# 171-5783.net
KiCad netlist of a schematic drawn in Altium Designer
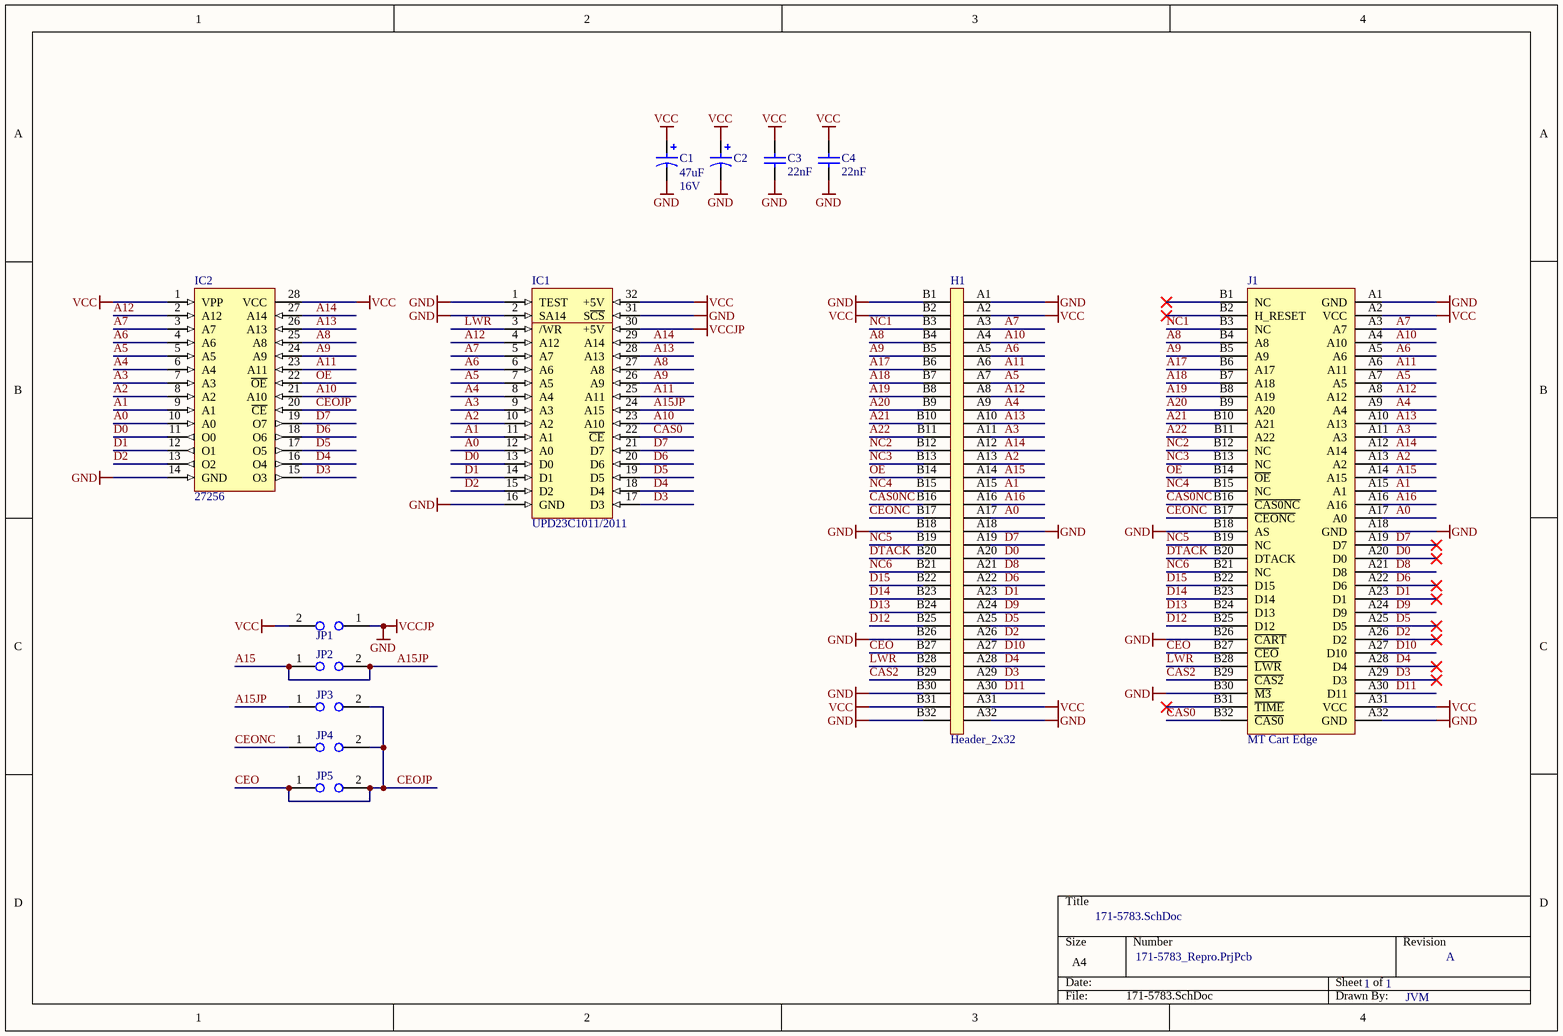
[diagram p0: 171-5783.SchDoc]

(export (version "E")
  (design (tool "Eeschema 10.0.6"))
  (components
    (comp (ref "C1")
      (value "47uF")
      (footprint "CapPol Mirror")
      (description "Polarized Capacitor, 2.54mm Pitch, 5mm Width, mirrored")
      (fields (field (name "VOLTAGE") "16V") (field (name "Comment") "Cap2.54P5.0D"))
      (libsource (lib "171-5782") (part "Cap2.54P5.0D_mirror"))
    )
    (comp (ref "C2")
      (value "Cap2.54P5.0D")
      (footprint "CapPol")
      (description "Polarized Capacitor, 2.54mm Pitch, 5mm Width")
      (libsource (lib "171-5782") (part "Cap2.54P5.0D"))
    )
    (comp (ref "C3")
      (value "22nF")
      (footprint "CapCer")
      (description "Capacitor (THT), Ceramic, 5.08mm Pitch")
      (fields (field (name "Comment") "CapCer"))
      (libsource (lib "171-5782") (part "CapCer"))
    )
    (comp (ref "C4")
      (value "22nF")
      (footprint "CapCer")
      (description "Capacitor (THT), Ceramic, 5.08mm Pitch")
      (fields (field (name "Comment") "CapCer"))
      (libsource (lib "171-5782") (part "CapCer"))
    )
    (comp (ref "H1")
      (value "Header_2x32")
      (footprint "Header_2x32")
      (libsource (lib "171-5782") (part "Header_2x32"))
    )
    (comp (ref "IC1")
      (value "UPD23C1011/2011")
      (footprint "UPD23C1011/2011")
      (description "SMS Mapper Mask Rom, Dual footprint")
      (libsource (lib "171-5782") (part "UPD23C1011/2011"))
    )
    (comp (ref "IC2")
      (value "27256")
      (footprint "27256")
      (description "256K EPROM")
      (libsource (lib "171-5782") (part "27256"))
    )
    (comp (ref "J1")
      (value "MT Cart Edge")
      (footprint "MT_Cart_Edge")
      (libsource (lib "171-5782") (part "MT_CART_EDGE_CON"))
    )
    (comp (ref "JP1")
      (value "SolderBridge")
      (footprint "SOLDER_BRIDGE")
      (description "Solder Bridge")
      (libsource (lib "171-5782") (part "SolderBridge"))
    )
    (comp (ref "JP2")
      (value "SolderBridge")
      (footprint "SOLDER_BRIDGE")
      (description "Solder Bridge")
      (libsource (lib "171-5782") (part "SolderBridge"))
    )
    (comp (ref "JP3")
      (value "SolderBridge")
      (footprint "SOLDER_BRIDGE")
      (description "Solder Bridge")
      (libsource (lib "171-5782") (part "SolderBridge"))
    )
    (comp (ref "JP4")
      (value "SolderBridge")
      (footprint "SOLDER_BRIDGE")
      (description "Solder Bridge")
      (libsource (lib "171-5782") (part "SolderBridge"))
    )
    (comp (ref "JP5")
      (value "SolderBridge")
      (footprint "SOLDER_BRIDGE")
      (description "Solder Bridge")
      (libsource (lib "171-5782") (part "SolderBridge"))
    )
  )
  (nets
    (net (code "1") (name "/A0") (class "Default")
      (node (ref "H1") (pin "A17") (pintype "passive"))
      (node (ref "IC1") (pin "12") (pinfunction "A0_12") (pintype "input"))
      (node (ref "IC2") (pin "10") (pinfunction "A0_10") (pintype "input"))
      (node (ref "J1") (pin "A17") (pinfunction "A0_A17") (pintype "passive"))
    )
    (net (code "2") (name "/A1") (class "Default")
      (node (ref "H1") (pin "A15") (pintype "passive"))
      (node (ref "IC1") (pin "11") (pinfunction "A1_11") (pintype "input"))
      (node (ref "IC2") (pin "9") (pinfunction "A1_9") (pintype "input"))
      (node (ref "J1") (pin "A15") (pinfunction "A1_A15") (pintype "passive"))
    )
    (net (code "3") (name "/A2") (class "Default")
      (node (ref "H1") (pin "A13") (pintype "passive"))
      (node (ref "IC1") (pin "10") (pinfunction "A2_10") (pintype "input"))
      (node (ref "IC2") (pin "8") (pinfunction "A2_8") (pintype "input"))
      (node (ref "J1") (pin "A13") (pinfunction "A2_A13") (pintype "passive"))
    )
    (net (code "4") (name "/A3") (class "Default")
      (node (ref "H1") (pin "A11") (pintype "passive"))
      (node (ref "IC1") (pin "9") (pinfunction "A3_9") (pintype "input"))
      (node (ref "IC2") (pin "7") (pinfunction "A3_7") (pintype "input"))
      (node (ref "J1") (pin "A11") (pinfunction "A3_A11") (pintype "passive"))
    )
    (net (code "5") (name "/A4") (class "Default")
      (node (ref "H1") (pin "A9") (pintype "passive"))
      (node (ref "IC1") (pin "8") (pinfunction "A4_8") (pintype "input"))
      (node (ref "IC2") (pin "6") (pinfunction "A4_6") (pintype "input"))
      (node (ref "J1") (pin "A9") (pinfunction "A4_A9") (pintype "passive"))
    )
    (net (code "6") (name "/A5") (class "Default")
      (node (ref "H1") (pin "A7") (pintype "passive"))
      (node (ref "IC1") (pin "7") (pinfunction "A5_7") (pintype "input"))
      (node (ref "IC2") (pin "5") (pinfunction "A5_5") (pintype "input"))
      (node (ref "J1") (pin "A7") (pinfunction "A5_A7") (pintype "passive"))
    )
    (net (code "7") (name "/A6") (class "Default")
      (node (ref "H1") (pin "A5") (pintype "passive"))
      (node (ref "IC1") (pin "6") (pinfunction "A6_6") (pintype "input"))
      (node (ref "IC2") (pin "4") (pinfunction "A6_4") (pintype "input"))
      (node (ref "J1") (pin "A5") (pinfunction "A6_A5") (pintype "passive"))
    )
    (net (code "8") (name "/A7") (class "Default")
      (node (ref "H1") (pin "A3") (pintype "passive"))
      (node (ref "IC1") (pin "5") (pinfunction "A7_5") (pintype "input"))
      (node (ref "IC2") (pin "3") (pinfunction "A7_3") (pintype "input"))
      (node (ref "J1") (pin "A3") (pinfunction "A7_A3") (pintype "passive"))
    )
    (net (code "9") (name "/A8") (class "Default")
      (node (ref "H1") (pin "B4") (pintype "passive"))
      (node (ref "IC1") (pin "27") (pinfunction "A8_27") (pintype "input"))
      (node (ref "IC2") (pin "25") (pinfunction "A8_25") (pintype "input"))
      (node (ref "J1") (pin "B4") (pinfunction "A8_B4") (pintype "passive"))
    )
    (net (code "10") (name "/A9") (class "Default")
      (node (ref "H1") (pin "B5") (pintype "passive"))
      (node (ref "IC1") (pin "26") (pinfunction "A9_26") (pintype "input"))
      (node (ref "IC2") (pin "24") (pinfunction "A9_24") (pintype "input"))
      (node (ref "J1") (pin "B5") (pinfunction "A9_B5") (pintype "passive"))
    )
    (net (code "11") (name "/A10") (class "Default")
      (node (ref "H1") (pin "A4") (pintype "passive"))
      (node (ref "IC1") (pin "23") (pinfunction "A10_23") (pintype "input"))
      (node (ref "IC2") (pin "21") (pinfunction "A10_21") (pintype "input"))
      (node (ref "J1") (pin "A4") (pinfunction "A10_A4") (pintype "passive"))
    )
    (net (code "12") (name "/A11") (class "Default")
      (node (ref "H1") (pin "A6") (pintype "passive"))
      (node (ref "IC1") (pin "25") (pinfunction "A11_25") (pintype "input"))
      (node (ref "IC2") (pin "23") (pinfunction "A11_23") (pintype "input"))
      (node (ref "J1") (pin "A6") (pinfunction "A11_A6") (pintype "passive"))
    )
    (net (code "13") (name "/A12") (class "Default")
      (node (ref "H1") (pin "A8") (pintype "passive"))
      (node (ref "IC1") (pin "4") (pinfunction "A12_4") (pintype "input"))
      (node (ref "IC2") (pin "2") (pinfunction "A12_2") (pintype "input"))
      (node (ref "J1") (pin "A8") (pinfunction "A12_A8") (pintype "passive"))
    )
    (net (code "14") (name "/A13") (class "Default")
      (node (ref "H1") (pin "A10") (pintype "passive"))
      (node (ref "IC1") (pin "28") (pinfunction "A13_28") (pintype "input"))
      (node (ref "IC2") (pin "26") (pinfunction "A13_26") (pintype "input"))
      (node (ref "J1") (pin "A10") (pinfunction "A13_A10") (pintype "passive"))
    )
    (net (code "15") (name "/A14") (class "Default")
      (node (ref "H1") (pin "A12") (pintype "passive"))
      (node (ref "IC1") (pin "29") (pinfunction "A14_29") (pintype "input"))
      (node (ref "IC2") (pin "27") (pinfunction "A14_27") (pintype "input"))
      (node (ref "J1") (pin "A12") (pinfunction "A14_A12") (pintype "passive"))
    )
    (net (code "16") (name "/A15") (class "Default")
      (node (ref "H1") (pin "A14") (pintype "passive"))
      (node (ref "IC1") (pin "24") (pinfunction "A15_24") (pintype "input"))
      (node (ref "J1") (pin "A14") (pinfunction "A15_A14") (pintype "passive"))
      (node (ref "JP2") (pin "1") (pinfunction "1_1") (pintype "passive"))
      (node (ref "JP2") (pin "2") (pinfunction "2_2") (pintype "passive"))
      (node (ref "JP3") (pin "1") (pinfunction "1_1") (pintype "passive"))
    )
    (net (code "17") (name "/A16") (class "Default")
      (node (ref "H1") (pin "A16") (pintype "passive"))
      (node (ref "J1") (pin "A16") (pinfunction "A16_A16") (pintype "passive"))
    )
    (net (code "18") (name "/A17") (class "Default")
      (node (ref "H1") (pin "B6") (pintype "passive"))
      (node (ref "J1") (pin "B6") (pinfunction "A17_B6") (pintype "passive"))
    )
    (net (code "19") (name "/A18") (class "Default")
      (node (ref "H1") (pin "B7") (pintype "passive"))
      (node (ref "J1") (pin "B7") (pinfunction "A18_B7") (pintype "passive"))
    )
    (net (code "20") (name "/A19") (class "Default")
      (node (ref "H1") (pin "B8") (pintype "passive"))
      (node (ref "J1") (pin "B8") (pinfunction "A19_B8") (pintype "passive"))
    )
    (net (code "21") (name "/A20") (class "Default")
      (node (ref "H1") (pin "B9") (pintype "passive"))
      (node (ref "J1") (pin "B9") (pinfunction "A20_B9") (pintype "passive"))
    )
    (net (code "22") (name "/A21") (class "Default")
      (node (ref "H1") (pin "B10") (pintype "passive"))
      (node (ref "J1") (pin "B10") (pinfunction "A21_B10") (pintype "passive"))
    )
    (net (code "23") (name "/A22") (class "Default")
      (node (ref "H1") (pin "B11") (pintype "passive"))
      (node (ref "J1") (pin "B11") (pinfunction "A22_B11") (pintype "passive"))
    )
    (net (code "24") (name "/CAS0") (class "Default")
      (node (ref "IC1") (pin "22") (pinfunction "~{CE}_22") (pintype "input"))
      (node (ref "J1") (pin "B32") (pinfunction "~{CAS0}_B32") (pintype "passive"))
    )
    (net (code "25") (name "/CAS0NC") (class "Default")
      (node (ref "H1") (pin "B16") (pintype "passive"))
      (node (ref "J1") (pin "B16") (pinfunction "~{CAS0NC}_B16") (pintype "passive"))
    )
    (net (code "26") (name "/CAS2") (class "Default")
      (node (ref "H1") (pin "B29") (pintype "passive"))
      (node (ref "J1") (pin "B29") (pinfunction "~{CAS2}_B29") (pintype "passive"))
    )
    (net (code "27") (name "/CEO") (class "Default")
      (node (ref "H1") (pin "B27") (pintype "passive"))
      (node (ref "IC2") (pin "20") (pinfunction "~{CE}_20") (pintype "input"))
      (node (ref "J1") (pin "B27") (pinfunction "~{CEO}_B27") (pintype "passive"))
      (node (ref "JP3") (pin "2") (pinfunction "2_2") (pintype "passive"))
      (node (ref "JP4") (pin "2") (pinfunction "2_2") (pintype "passive"))
      (node (ref "JP5") (pin "1") (pinfunction "1_1") (pintype "passive"))
      (node (ref "JP5") (pin "2") (pinfunction "2_2") (pintype "passive"))
    )
    (net (code "28") (name "/CEONC") (class "Default")
      (node (ref "H1") (pin "B17") (pintype "passive"))
      (node (ref "J1") (pin "B17") (pinfunction "~{CEONC}_B17") (pintype "passive"))
      (node (ref "JP4") (pin "1") (pinfunction "1_1") (pintype "passive"))
    )
    (net (code "29") (name "/D0") (class "Default")
      (node (ref "H1") (pin "A20") (pintype "passive"))
      (node (ref "IC1") (pin "13") (pinfunction "D0_13") (pintype "input"))
      (node (ref "IC2") (pin "11") (pinfunction "O0_11") (pintype "output"))
      (node (ref "J1") (pin "A20") (pinfunction "D0_A20") (pintype "passive"))
    )
    (net (code "30") (name "/D1") (class "Default")
      (node (ref "H1") (pin "A23") (pintype "passive"))
      (node (ref "IC1") (pin "14") (pinfunction "D1_14") (pintype "input"))
      (node (ref "IC2") (pin "12") (pinfunction "O1_12") (pintype "output"))
      (node (ref "J1") (pin "A23") (pinfunction "D1_A23") (pintype "passive"))
    )
    (net (code "31") (name "/D2") (class "Default")
      (node (ref "H1") (pin "A26") (pintype "passive"))
      (node (ref "IC1") (pin "15") (pinfunction "D2_15") (pintype "input"))
      (node (ref "IC2") (pin "13") (pinfunction "O2_13") (pintype "output"))
      (node (ref "J1") (pin "A26") (pinfunction "D2_A26") (pintype "passive"))
    )
    (net (code "32") (name "/D3") (class "Default")
      (node (ref "H1") (pin "A29") (pintype "passive"))
      (node (ref "IC1") (pin "17") (pinfunction "D3_17") (pintype "input"))
      (node (ref "IC2") (pin "15") (pinfunction "O3_15") (pintype "output"))
      (node (ref "J1") (pin "A29") (pinfunction "D3_A29") (pintype "passive"))
    )
    (net (code "33") (name "/D4") (class "Default")
      (node (ref "H1") (pin "A28") (pintype "passive"))
      (node (ref "IC1") (pin "18") (pinfunction "D4_18") (pintype "input"))
      (node (ref "IC2") (pin "16") (pinfunction "O4_16") (pintype "output"))
      (node (ref "J1") (pin "A28") (pinfunction "D4_A28") (pintype "passive"))
    )
    (net (code "34") (name "/D5") (class "Default")
      (node (ref "H1") (pin "A25") (pintype "passive"))
      (node (ref "IC1") (pin "19") (pinfunction "D5_19") (pintype "input"))
      (node (ref "IC2") (pin "17") (pinfunction "O5_17") (pintype "output"))
      (node (ref "J1") (pin "A25") (pinfunction "D5_A25") (pintype "passive"))
    )
    (net (code "35") (name "/D6") (class "Default")
      (node (ref "H1") (pin "A22") (pintype "passive"))
      (node (ref "IC1") (pin "20") (pinfunction "D6_20") (pintype "input"))
      (node (ref "IC2") (pin "18") (pinfunction "O6_18") (pintype "output"))
      (node (ref "J1") (pin "A22") (pinfunction "D6_A22") (pintype "passive"))
    )
    (net (code "36") (name "/D7") (class "Default")
      (node (ref "H1") (pin "A19") (pintype "passive"))
      (node (ref "IC1") (pin "21") (pinfunction "D7_21") (pintype "input"))
      (node (ref "IC2") (pin "19") (pinfunction "O7_19") (pintype "output"))
      (node (ref "J1") (pin "A19") (pinfunction "D7_A19") (pintype "passive"))
    )
    (net (code "37") (name "/D8") (class "Default")
      (node (ref "H1") (pin "A21") (pintype "passive"))
      (node (ref "J1") (pin "A21") (pinfunction "D8_A21") (pintype "passive"))
    )
    (net (code "38") (name "/D9") (class "Default")
      (node (ref "H1") (pin "A24") (pintype "passive"))
      (node (ref "J1") (pin "A24") (pinfunction "D9_A24") (pintype "passive"))
    )
    (net (code "39") (name "/D10") (class "Default")
      (node (ref "H1") (pin "A27") (pintype "passive"))
      (node (ref "J1") (pin "A27") (pinfunction "D10_A27") (pintype "passive"))
    )
    (net (code "40") (name "/D11") (class "Default")
      (node (ref "H1") (pin "A30") (pintype "passive"))
      (node (ref "J1") (pin "A30") (pinfunction "D11_A30") (pintype "passive"))
    )
    (net (code "41") (name "/D12") (class "Default")
      (node (ref "H1") (pin "B25") (pintype "passive"))
      (node (ref "J1") (pin "B25") (pinfunction "D12_B25") (pintype "passive"))
    )
    (net (code "42") (name "/D13") (class "Default")
      (node (ref "H1") (pin "B24") (pintype "passive"))
      (node (ref "J1") (pin "B24") (pinfunction "D13_B24") (pintype "passive"))
    )
    (net (code "43") (name "/D14") (class "Default")
      (node (ref "H1") (pin "B23") (pintype "passive"))
      (node (ref "J1") (pin "B23") (pinfunction "D14_B23") (pintype "passive"))
    )
    (net (code "44") (name "/D15") (class "Default")
      (node (ref "H1") (pin "B22") (pintype "passive"))
      (node (ref "J1") (pin "B22") (pinfunction "D15_B22") (pintype "passive"))
    )
    (net (code "45") (name "/DTACK") (class "Default")
      (node (ref "H1") (pin "B20") (pintype "passive"))
      (node (ref "J1") (pin "B20") (pinfunction "DTACK_B20") (pintype "passive"))
    )
    (net (code "46") (name "/LWR") (class "Default")
      (node (ref "H1") (pin "B28") (pintype "passive"))
      (node (ref "IC1") (pin "3") (pinfunction "/WR_3") (pintype "input"))
      (node (ref "J1") (pin "B28") (pinfunction "~{LWR}_B28") (pintype "passive"))
    )
    (net (code "47") (name "/NC1") (class "Default")
      (node (ref "H1") (pin "B3") (pintype "passive"))
      (node (ref "J1") (pin "B3") (pinfunction "NC_B3") (pintype "passive"))
    )
    (net (code "48") (name "/NC2") (class "Default")
      (node (ref "H1") (pin "B12") (pintype "passive"))
      (node (ref "J1") (pin "B12") (pinfunction "NC_B12") (pintype "passive"))
    )
    (net (code "49") (name "/NC3") (class "Default")
      (node (ref "H1") (pin "B13") (pintype "passive"))
      (node (ref "J1") (pin "B13") (pinfunction "NC_B13") (pintype "passive"))
    )
    (net (code "50") (name "/NC4") (class "Default")
      (node (ref "H1") (pin "B15") (pintype "passive"))
      (node (ref "J1") (pin "B15") (pinfunction "NC_B15") (pintype "passive"))
    )
    (net (code "51") (name "/NC5") (class "Default")
      (node (ref "H1") (pin "B19") (pintype "passive"))
      (node (ref "J1") (pin "B19") (pinfunction "NC_B19") (pintype "passive"))
    )
    (net (code "52") (name "/NC6") (class "Default")
      (node (ref "H1") (pin "B21") (pintype "passive"))
      (node (ref "J1") (pin "B21") (pinfunction "NC_B21") (pintype "passive"))
    )
    (net (code "53") (name "/OE") (class "Default")
      (node (ref "H1") (pin "B14") (pintype "passive"))
      (node (ref "IC2") (pin "22") (pinfunction "~{OE}_22") (pintype "input"))
      (node (ref "J1") (pin "B14") (pinfunction "~{OE}_B14") (pintype "passive"))
    )
    (net (code "54") (name "GND") (class "Default")
      (node (ref "C1") (pin "2") (pinfunction "2_2") (pintype "passive"))
      (node (ref "C2") (pin "2") (pinfunction "2_2") (pintype "passive"))
      (node (ref "C3") (pin "1") (pinfunction "1_1") (pintype "passive"))
      (node (ref "C4") (pin "1") (pinfunction "1_1") (pintype "passive"))
      (node (ref "H1") (pin "A1") (pintype "passive"))
      (node (ref "H1") (pin "A18") (pintype "passive"))
      (node (ref "H1") (pin "A32") (pintype "passive"))
      (node (ref "H1") (pin "B1") (pintype "passive"))
      (node (ref "H1") (pin "B18") (pintype "passive"))
      (node (ref "H1") (pin "B26") (pintype "passive"))
      (node (ref "H1") (pin "B30") (pintype "passive"))
      (node (ref "H1") (pin "B32") (pintype "passive"))
      (node (ref "IC1") (pin "1") (pinfunction "TEST_1") (pintype "input"))
      (node (ref "IC1") (pin "16") (pinfunction "GND_16") (pintype "input"))
      (node (ref "IC1") (pin "2") (pinfunction "SA14_2") (pintype "input"))
      (node (ref "IC1") (pin "30") (pinfunction "+5V_30") (pintype "input"))
      (node (ref "IC1") (pin "31") (pinfunction "S~{CS}_31") (pintype "input"))
      (node (ref "IC2") (pin "14") (pinfunction "GND_14") (pintype "input"))
      (node (ref "J1") (pin "A1") (pinfunction "GND_A1") (pintype "passive"))
      (node (ref "J1") (pin "A18") (pinfunction "GND_A18") (pintype "passive"))
      (node (ref "J1") (pin "A32") (pinfunction "GND_A32") (pintype "passive"))
      (node (ref "J1") (pin "B18") (pinfunction "AS_B18") (pintype "passive"))
      (node (ref "J1") (pin "B26") (pinfunction "~{CART}_B26") (pintype "passive"))
      (node (ref "J1") (pin "B30") (pinfunction "~{M3}_B30") (pintype "passive"))
      (node (ref "JP1") (pin "1") (pinfunction "1_1") (pintype "passive"))
    )
    (net (code "55") (name "VCC") (class "Default")
      (node (ref "C1") (pin "1") (pinfunction "1_1") (pintype "passive"))
      (node (ref "C2") (pin "1") (pinfunction "1_1") (pintype "passive"))
      (node (ref "C3") (pin "2") (pinfunction "2_2") (pintype "passive"))
      (node (ref "C4") (pin "2") (pinfunction "2_2") (pintype "passive"))
      (node (ref "H1") (pin "A2") (pintype "passive"))
      (node (ref "H1") (pin "A31") (pintype "passive"))
      (node (ref "H1") (pin "B2") (pintype "passive"))
      (node (ref "H1") (pin "B31") (pintype "passive"))
      (node (ref "IC1") (pin "32") (pinfunction "+5V_32") (pintype "input"))
      (node (ref "IC2") (pin "1") (pinfunction "VPP_1") (pintype "input"))
      (node (ref "IC2") (pin "28") (pinfunction "VCC_28") (pintype "power_in"))
      (node (ref "J1") (pin "A2") (pinfunction "VCC_A2") (pintype "passive"))
      (node (ref "J1") (pin "A31") (pinfunction "VCC_A31") (pintype "passive"))
      (node (ref "JP1") (pin "2") (pinfunction "2_2") (pintype "passive"))
    )
    (net (code "56") (name "unconnected-(J1-H_RESET-PadB2)") (class "Default")
      (node (ref "J1") (pin "B2") (pinfunction "H_RESET_B2") (pintype "passive+no_connect"))
    )
    (net (code "57") (name "unconnected-(J1-NC-PadB1)") (class "Default")
      (node (ref "J1") (pin "B1") (pinfunction "NC_B1") (pintype "passive+no_connect"))
    )
    (net (code "58") (name "unconnected-(J1-~{TIME}-PadB31)") (class "Default")
      (node (ref "J1") (pin "B31") (pinfunction "~{TIME}_B31") (pintype "passive+no_connect"))
    )
  )
)
